# SuperSensors.net
KiCad netlist of a schematic drawn in EAGLE
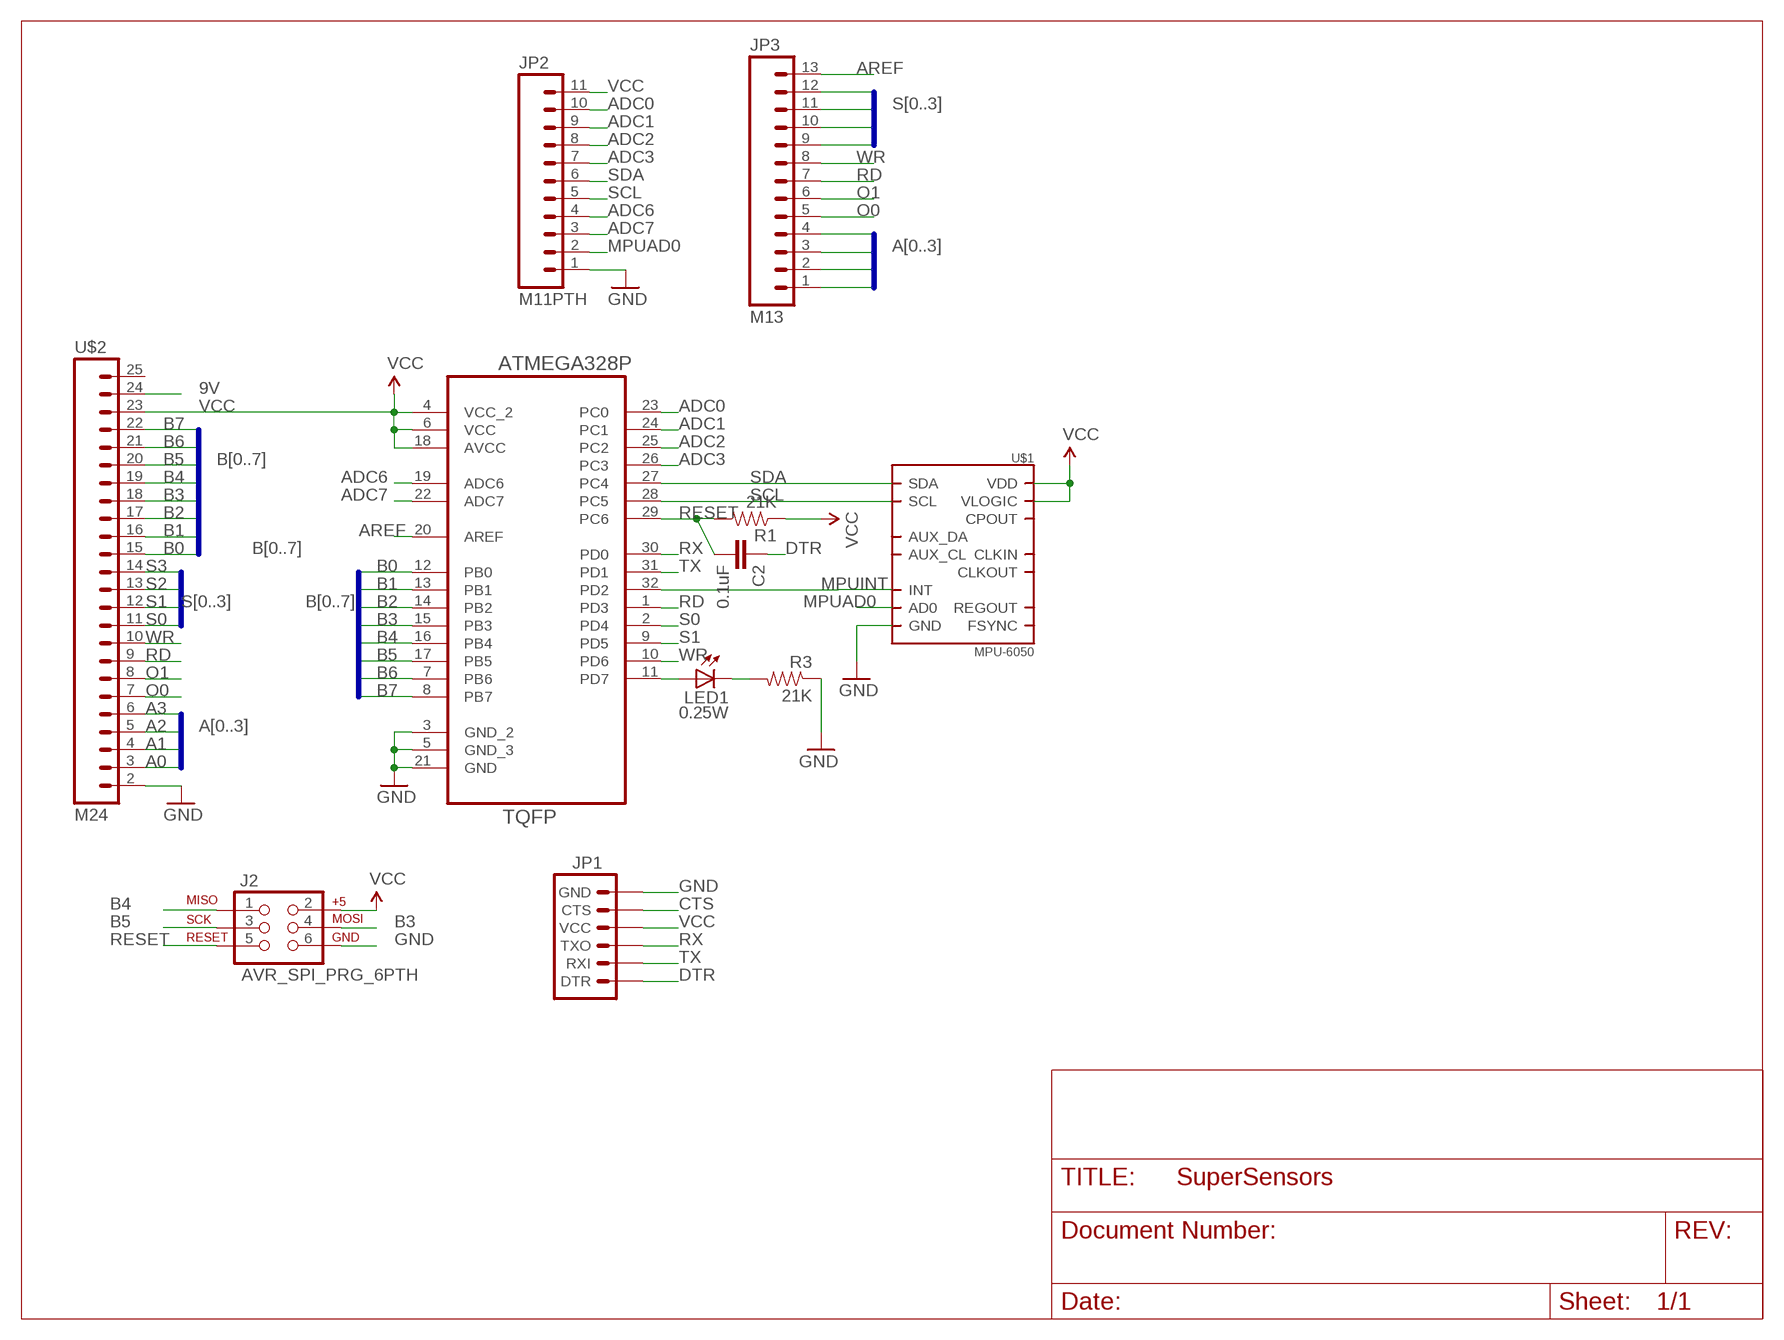
[diagram p0: schematic, sheet 1]

(export (version "E")
  (design (tool "Eeschema 10.0.6"))
  (components
    (comp (ref "C2")
      (value "0.1uF")
      (footprint "eagle-import:CAP-PTH-SMALL")
      (libsource (lib "eagle-import") (part "CAPPTH"))
    )
    (comp (ref "J2")
      (value "AVR_SPI_PRG_6PTH")
      (footprint "eagle-import:2X3")
      (libsource (lib "eagle-import") (part "AVR_SPI_PRG_6PTH"))
    )
    (comp (ref "JP1")
      (value "ARDUINO_SERIAL_PROGRAMPTH")
      (footprint "eagle-import:1X06")
      (libsource (lib "eagle-import") (part "ARDUINO_SERIAL_PROGRAMPTH"))
    )
    (comp (ref "JP2")
      (value "M11PTH")
      (footprint "eagle-import:1X11")
      (libsource (lib "eagle-import") (part "M11PTH"))
    )
    (comp (ref "JP3")
      (value "M13")
      (footprint "eagle-import:1X13")
      (libsource (lib "eagle-import") (part "M13"))
    )
    (comp (ref "LED1")
      (value "0.25W")
      (footprint "eagle-import:LED5MM")
      (libsource (lib "eagle-import") (part "LED5MM"))
    )
    (comp (ref "R1")
      (value "21K")
      (footprint "eagle-import:AXIAL-0.4")
      (libsource (lib "eagle-import") (part "RESISTORPTH-1/4W"))
    )
    (comp (ref "R3")
      (value "21K")
      (footprint "eagle-import:AXIAL-0.4")
      (libsource (lib "eagle-import") (part "RESISTORPTH-1/4W"))
    )
    (comp (ref "U$1")
      (value "MPU-6050")
      (footprint "eagle-import:QFN.24.4X4")
      (libsource (lib "eagle-import") (part "MPU-6050"))
    )
    (comp (ref "U$2")
      (value "M24")
      (footprint "eagle-import:1X24")
      (libsource (lib "eagle-import") (part "M24"))
    )
    (comp (ref "U1")
      (value "ATMEGA328P-AU")
      (footprint "eagle-import:QFP80P900X900X120-32N")
      (libsource (lib "eagle-import") (part "ATMEGA328P-AU"))
    )
  )
  (nets
    (net (code "1") (name "/9V") (class "Default")
      (node (ref "U$2") (pin "24") (pinfunction "24_24") (pintype "passive"))
    )
    (net (code "2") (name "/A0") (class "Default")
      (node (ref "JP3") (pin "1") (pinfunction "1_1") (pintype "passive"))
      (node (ref "U$2") (pin "3") (pinfunction "3_3") (pintype "passive"))
    )
    (net (code "3") (name "/A1") (class "Default")
      (node (ref "JP3") (pin "2") (pinfunction "2_2") (pintype "passive"))
      (node (ref "U$2") (pin "4") (pinfunction "4_4") (pintype "passive"))
    )
    (net (code "4") (name "/A2") (class "Default")
      (node (ref "JP3") (pin "3") (pinfunction "3_3") (pintype "passive"))
      (node (ref "U$2") (pin "5") (pinfunction "5_5") (pintype "passive"))
    )
    (net (code "5") (name "/A3") (class "Default")
      (node (ref "JP3") (pin "4") (pinfunction "4_4") (pintype "passive"))
      (node (ref "U$2") (pin "6") (pinfunction "6_6") (pintype "passive"))
    )
    (net (code "6") (name "/ADC0") (class "Default")
      (node (ref "JP2") (pin "10") (pinfunction "10_10") (pintype "passive"))
      (node (ref "U1") (pin "23") (pinfunction "PC0_23") (pintype "bidirectional"))
    )
    (net (code "7") (name "/ADC1") (class "Default")
      (node (ref "JP2") (pin "9") (pinfunction "9_9") (pintype "passive"))
      (node (ref "U1") (pin "24") (pinfunction "PC1_24") (pintype "bidirectional"))
    )
    (net (code "8") (name "/ADC2") (class "Default")
      (node (ref "JP2") (pin "8") (pinfunction "8_8") (pintype "passive"))
      (node (ref "U1") (pin "25") (pinfunction "PC2_25") (pintype "bidirectional"))
    )
    (net (code "9") (name "/ADC3") (class "Default")
      (node (ref "JP2") (pin "7") (pinfunction "7_7") (pintype "passive"))
      (node (ref "U1") (pin "26") (pinfunction "PC3_26") (pintype "bidirectional"))
    )
    (net (code "10") (name "/ADC6") (class "Default")
      (node (ref "JP2") (pin "4") (pinfunction "4_4") (pintype "passive"))
      (node (ref "U1") (pin "19") (pinfunction "ADC6_19") (pintype "input"))
    )
    (net (code "11") (name "/ADC7") (class "Default")
      (node (ref "JP2") (pin "3") (pinfunction "3_3") (pintype "passive"))
      (node (ref "U1") (pin "22") (pinfunction "ADC7_22") (pintype "input"))
    )
    (net (code "12") (name "/AREF") (class "Default")
      (node (ref "JP3") (pin "13") (pinfunction "13_13") (pintype "passive"))
      (node (ref "U1") (pin "20") (pinfunction "AREF_20") (pintype "input"))
    )
    (net (code "14") (name "/B0") (class "Default")
      (node (ref "U$2") (pin "15") (pinfunction "15_15") (pintype "passive"))
      (node (ref "U1") (pin "12") (pinfunction "PB0_12") (pintype "bidirectional"))
    )
    (net (code "15") (name "/B1") (class "Default")
      (node (ref "U$2") (pin "16") (pinfunction "16_16") (pintype "passive"))
      (node (ref "U1") (pin "13") (pinfunction "PB1_13") (pintype "bidirectional"))
    )
    (net (code "16") (name "/B2") (class "Default")
      (node (ref "U$2") (pin "17") (pinfunction "17_17") (pintype "passive"))
      (node (ref "U1") (pin "14") (pinfunction "PB2_14") (pintype "bidirectional"))
    )
    (net (code "17") (name "/B3") (class "Default")
      (node (ref "J2") (pin "4") (pinfunction "4_4") (pintype "passive"))
      (node (ref "U$2") (pin "18") (pinfunction "18_18") (pintype "passive"))
      (node (ref "U1") (pin "15") (pinfunction "PB3_15") (pintype "bidirectional"))
    )
    (net (code "18") (name "/B4") (class "Default")
      (node (ref "J2") (pin "1") (pinfunction "1_1") (pintype "passive"))
      (node (ref "U$2") (pin "19") (pinfunction "19_19") (pintype "passive"))
      (node (ref "U1") (pin "16") (pinfunction "PB4_16") (pintype "bidirectional"))
    )
    (net (code "19") (name "/B5") (class "Default")
      (node (ref "J2") (pin "3") (pinfunction "3_3") (pintype "passive"))
      (node (ref "U$2") (pin "20") (pinfunction "20_20") (pintype "passive"))
      (node (ref "U1") (pin "17") (pinfunction "PB5_17") (pintype "bidirectional"))
    )
    (net (code "20") (name "/B6") (class "Default")
      (node (ref "U$2") (pin "21") (pinfunction "21_21") (pintype "passive"))
      (node (ref "U1") (pin "7") (pinfunction "PB6_7") (pintype "bidirectional"))
    )
    (net (code "21") (name "/B7") (class "Default")
      (node (ref "U$2") (pin "22") (pinfunction "22_22") (pintype "passive"))
      (node (ref "U1") (pin "8") (pinfunction "PB7_8") (pintype "bidirectional"))
    )
    (net (code "23") (name "/CTS") (class "Default")
      (node (ref "JP1") (pin "5") (pinfunction "CTS_5") (pintype "passive"))
    )
    (net (code "24") (name "/DTR") (class "Default")
      (node (ref "C2") (pin "1") (pinfunction "1_1") (pintype "passive"))
      (node (ref "JP1") (pin "1") (pinfunction "DTR_1") (pintype "passive"))
    )
    (net (code "25") (name "/MPUAD0") (class "Default")
      (node (ref "JP2") (pin "2") (pinfunction "2_2") (pintype "passive"))
      (node (ref "U$1") (pin "9") (pinfunction "AD0_9") (pintype "bidirectional"))
    )
    (net (code "26") (name "/MPUINT") (class "Default")
      (node (ref "U$1") (pin "12") (pinfunction "INT_12") (pintype "bidirectional"))
      (node (ref "U1") (pin "32") (pinfunction "PD2_32") (pintype "bidirectional"))
    )
    (net (code "27") (name "/O0") (class "Default")
      (node (ref "JP3") (pin "5") (pinfunction "5_5") (pintype "passive"))
      (node (ref "U$2") (pin "7") (pinfunction "7_7") (pintype "passive"))
    )
    (net (code "28") (name "/O1") (class "Default")
      (node (ref "JP3") (pin "6") (pinfunction "6_6") (pintype "passive"))
      (node (ref "U$2") (pin "8") (pinfunction "8_8") (pintype "passive"))
    )
    (net (code "29") (name "/RD") (class "Default")
      (node (ref "JP3") (pin "7") (pinfunction "7_7") (pintype "passive"))
      (node (ref "U$2") (pin "9") (pinfunction "9_9") (pintype "passive"))
      (node (ref "U1") (pin "1") (pinfunction "PD3_1") (pintype "bidirectional"))
    )
    (net (code "30") (name "/RESET") (class "Default")
      (node (ref "C2") (pin "2") (pinfunction "2_2") (pintype "passive"))
      (node (ref "J2") (pin "5") (pinfunction "5_5") (pintype "passive"))
      (node (ref "R1") (pin "P$2") (pinfunction "2_P$2") (pintype "passive"))
      (node (ref "U1") (pin "29") (pinfunction "PC6_29") (pintype "bidirectional"))
    )
    (net (code "31") (name "/RX") (class "Default")
      (node (ref "JP1") (pin "3") (pinfunction "TXO_3") (pintype "passive"))
      (node (ref "U1") (pin "30") (pinfunction "PD0_30") (pintype "bidirectional"))
    )
    (net (code "32") (name "/S0") (class "Default")
      (node (ref "JP3") (pin "9") (pinfunction "9_9") (pintype "passive"))
      (node (ref "U$2") (pin "11") (pinfunction "11_11") (pintype "passive"))
      (node (ref "U1") (pin "2") (pinfunction "PD4_2") (pintype "bidirectional"))
    )
    (net (code "33") (name "/S1") (class "Default")
      (node (ref "JP3") (pin "10") (pinfunction "10_10") (pintype "passive"))
      (node (ref "U$2") (pin "12") (pinfunction "12_12") (pintype "passive"))
      (node (ref "U1") (pin "9") (pinfunction "PD5_9") (pintype "bidirectional"))
    )
    (net (code "34") (name "/S2") (class "Default")
      (node (ref "JP3") (pin "11") (pinfunction "11_11") (pintype "passive"))
      (node (ref "U$2") (pin "13") (pinfunction "13_13") (pintype "passive"))
    )
    (net (code "35") (name "/S3") (class "Default")
      (node (ref "JP3") (pin "12") (pinfunction "12_12") (pintype "passive"))
      (node (ref "U$2") (pin "14") (pinfunction "14_14") (pintype "passive"))
    )
    (net (code "36") (name "/SCL") (class "Default")
      (node (ref "JP2") (pin "5") (pinfunction "5_5") (pintype "passive"))
      (node (ref "U$1") (pin "23") (pinfunction "SCL_23") (pintype "bidirectional"))
      (node (ref "U1") (pin "28") (pinfunction "PC5_28") (pintype "bidirectional"))
    )
    (net (code "37") (name "/SDA") (class "Default")
      (node (ref "JP2") (pin "6") (pinfunction "6_6") (pintype "passive"))
      (node (ref "U$1") (pin "24") (pinfunction "SDA_24") (pintype "bidirectional"))
      (node (ref "U1") (pin "27") (pinfunction "PC4_27") (pintype "bidirectional"))
    )
    (net (code "39") (name "/TX") (class "Default")
      (node (ref "JP1") (pin "2") (pinfunction "RXI_2") (pintype "passive"))
      (node (ref "U1") (pin "31") (pinfunction "PD1_31") (pintype "bidirectional"))
    )
    (net (code "40") (name "/WR") (class "Default")
      (node (ref "JP3") (pin "8") (pinfunction "8_8") (pintype "passive"))
      (node (ref "U$2") (pin "10") (pinfunction "10_10") (pintype "passive"))
      (node (ref "U1") (pin "10") (pinfunction "PD6_10") (pintype "bidirectional"))
    )
    (net (code "41") (name "GND") (class "Default")
      (node (ref "J2") (pin "6") (pinfunction "6_6") (pintype "passive"))
      (node (ref "JP1") (pin "6") (pinfunction "GND_6") (pintype "passive"))
      (node (ref "JP2") (pin "1") (pinfunction "1_1") (pintype "passive"))
      (node (ref "R3") (pin "P$1") (pinfunction "1_P$1") (pintype "passive"))
      (node (ref "U$1") (pin "18") (pinfunction "GND_18") (pintype "bidirectional"))
      (node (ref "U$2") (pin "2") (pinfunction "2_2") (pintype "passive"))
      (node (ref "U1") (pin "21") (pinfunction "GND_21") (pintype "passive"))
      (node (ref "U1") (pin "3") (pinfunction "GND_2_3") (pintype "passive"))
      (node (ref "U1") (pin "5") (pinfunction "GND_3_5") (pintype "passive"))
    )
    (net (code "42") (name "Net-(LED1-C)") (class "Default")
      (node (ref "LED1") (pin "K") (pinfunction "C_K") (pintype "passive"))
      (node (ref "R3") (pin "P$2") (pinfunction "2_P$2") (pintype "passive"))
    )
    (net (code "43") (name "Net-(U1-PD7)") (class "Default")
      (node (ref "LED1") (pin "A") (pinfunction "A_A") (pintype "passive"))
      (node (ref "U1") (pin "11") (pinfunction "PD7_11") (pintype "bidirectional"))
    )
    (net (code "44") (name "VCC") (class "Default")
      (node (ref "J2") (pin "2") (pinfunction "2_2") (pintype "passive"))
      (node (ref "JP1") (pin "4") (pinfunction "VCC_4") (pintype "passive"))
      (node (ref "JP2") (pin "11") (pinfunction "11_11") (pintype "passive"))
      (node (ref "R1") (pin "P$1") (pinfunction "1_P$1") (pintype "passive"))
      (node (ref "U$1") (pin "13") (pinfunction "VDD_13") (pintype "bidirectional"))
      (node (ref "U$1") (pin "8") (pinfunction "VLOGIC_8") (pintype "bidirectional"))
      (node (ref "U$2") (pin "23") (pinfunction "23_23") (pintype "passive"))
      (node (ref "U1") (pin "18") (pinfunction "AVCC_18") (pintype "power_in"))
      (node (ref "U1") (pin "4") (pinfunction "VCC_2_4") (pintype "power_in"))
      (node (ref "U1") (pin "6") (pinfunction "VCC_6") (pintype "power_in"))
    )
    (net (code "45") (name "unconnected-(U$1-AUX_CL-Pad7)") (class "Default")
      (node (ref "U$1") (pin "7") (pinfunction "AUX_CL_7") (pintype "bidirectional"))
    )
    (net (code "46") (name "unconnected-(U$1-AUX_DA-Pad6)") (class "Default")
      (node (ref "U$1") (pin "6") (pinfunction "AUX_DA_6") (pintype "bidirectional"))
    )
    (net (code "47") (name "unconnected-(U$1-CLKIN-Pad1)") (class "Default")
      (node (ref "U$1") (pin "1") (pinfunction "CLKIN_1") (pintype "bidirectional"))
    )
    (net (code "48") (name "unconnected-(U$1-CLKOUT-Pad22)") (class "Default")
      (node (ref "U$1") (pin "22") (pinfunction "CLKOUT_22") (pintype "bidirectional"))
    )
    (net (code "49") (name "unconnected-(U$1-CPOUT-Pad20)") (class "Default")
      (node (ref "U$1") (pin "20") (pinfunction "CPOUT_20") (pintype "bidirectional"))
    )
    (net (code "50") (name "unconnected-(U$1-FSYNC-Pad11)") (class "Default")
      (node (ref "U$1") (pin "11") (pinfunction "FSYNC_11") (pintype "bidirectional"))
    )
    (net (code "51") (name "unconnected-(U$1-REGOUT-Pad10)") (class "Default")
      (node (ref "U$1") (pin "10") (pinfunction "REGOUT_10") (pintype "bidirectional"))
    )
    (net (code "52") (name "unconnected-(U$2-Pad25)") (class "Default")
      (node (ref "U$2") (pin "25") (pinfunction "25_25") (pintype "passive"))
    )
  )
)
